# 1_panel.net
KiCad netlist of a schematic drawn in Altium Designer
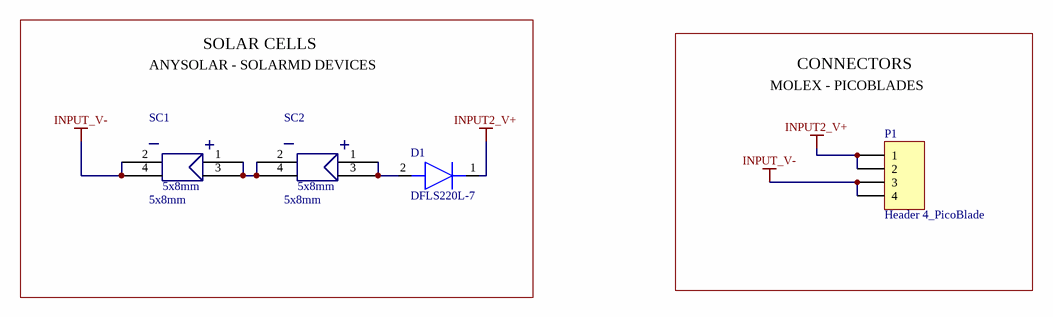
[diagram p0: 1_panel.schdoc]

(export (version "E")
  (design (tool "Eeschema 10.0.6"))
  (components
    (comp (ref "D1")
      (value "DFLS220L-7")
      (footprint "DFLS220L7")
      (description "Diode")
      (fields (field (name "MOUSER PART NUMBER") "621-DFLS220L-7"))
      (libsource (lib "*") (part "DFLS220L-7"))
    )
    (comp (ref "P1")
      (value "Header 4_PicoBlade")
      (footprint "PICOBLADE 4PIN VERTICAL - duplicate")
      (description "Header, 4-Pin")
      (fields
        (field (name "PARTNUMBER") "53398-0471")
        (field (name "MANUFACTURER") "Molex")
        (field (name "PUBLISHER") "Altium Limited")
      )
      (libsource (lib "PCB_Project_FlightModel_EPS") (part "Header 4_PicoBlade"))
    )
    (comp (ref "SC1")
      (value "5x8mm")
      (footprint "SOLAR_CELL")
      (fields (field (name "MANUFACTURER") "Yim Space"))
      (libsource (lib "Schlib1") (part "SOLAR CELL"))
    )
    (comp (ref "SC2")
      (value "5x8mm")
      (footprint "SOLAR_CELL")
      (fields (field (name "MANUFACTURER") "Yim Space"))
      (libsource (lib "Schlib1") (part "SOLAR CELL"))
    )
  )
  (nets
    (net (code "1") (name "INPUT2_V+") (class "Default")
      (node (ref "D1") (pin "1") (pinfunction "K_1") (pintype "passive"))
      (node (ref "P1") (pin "1") (pinfunction "1_1") (pintype "passive"))
      (node (ref "P1") (pin "2") (pinfunction "2_2") (pintype "passive"))
    )
    (net (code "2") (name "INPUT_V-") (class "Default")
      (node (ref "P1") (pin "3") (pinfunction "3_3") (pintype "passive"))
      (node (ref "P1") (pin "4") (pinfunction "4_4") (pintype "passive"))
      (node (ref "SC1") (pin "2") (pinfunction "V-_2") (pintype "power_in"))
      (node (ref "SC1") (pin "4") (pinfunction "4_4") (pintype "passive"))
    )
    (net (code "3") (name "Net-(D1-A)") (class "Default")
      (node (ref "D1") (pin "2") (pinfunction "A_2") (pintype "passive"))
      (node (ref "SC2") (pin "1") (pinfunction "V+_1") (pintype "power_in"))
      (node (ref "SC2") (pin "3") (pinfunction "3_3") (pintype "passive"))
    )
    (net (code "4") (name "Net-(SC1-V+)") (class "Default")
      (node (ref "SC1") (pin "1") (pinfunction "V+_1") (pintype "power_in"))
      (node (ref "SC1") (pin "3") (pinfunction "3_3") (pintype "passive"))
      (node (ref "SC2") (pin "2") (pinfunction "V-_2") (pintype "power_in"))
      (node (ref "SC2") (pin "4") (pinfunction "4_4") (pintype "passive"))
    )
  )
)
